# User_Interface.net
KiCad netlist of a schematic drawn in Altium Designer
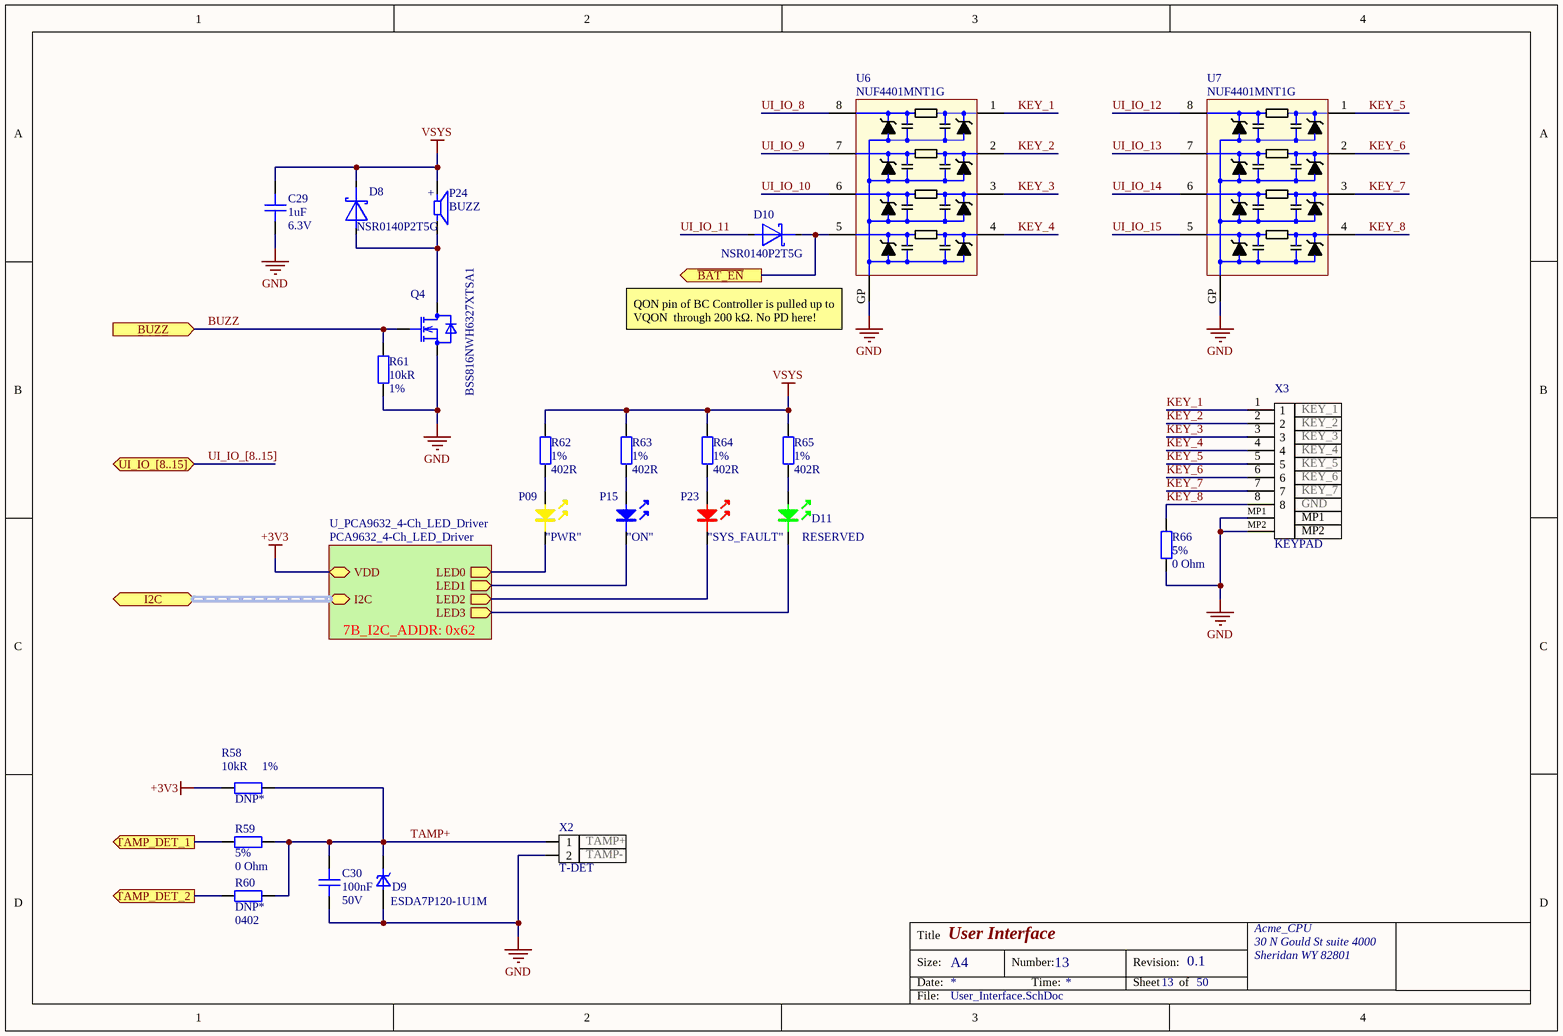
[diagram p0: User_Interface.SchDoc]

(export (version "E")
  (design (tool "Eeschema 10.0.6"))
  (components
    (comp (ref "C29")
      (value "CAP CER 1UF 6.3V X5R 0402")
      (footprint "C0402")
      (description "1µF ±10% 6.3V Ceramic Capacitor X5R 0402 (1005 Metric)")
      (fields
        (field (name "MANUFACTURER") "Yageo")
        (field (name "MANUFACTURER PART NUMBER") "CC0402KRX5R5BB105")
        (field (name "CAPACITANCE") "1uF")
        (field (name "VOLTAGE RATING") "6.3V")
      )
      (libsource (lib "capacitors_smd") (part "CAP CER 1UF 6.3V X5R 0402"))
    )
    (comp (ref "C30")
      (value "CAP CER 0.1UF 50V X7R 0402")
      (footprint "C0402")
      (description "0.1µF ±10% 50V Ceramic Capacitor X7R 0402 (1005 Metric)")
      (fields
        (field (name "MANUFACTURER") "TDK")
        (field (name "MANUFACTURER PART NUMBER") "CGA2B3X7R1H104K050BB")
        (field (name "CAPACITANCE") "100nF")
        (field (name "VOLTAGE") "50V")
      )
      (libsource (lib "capacitors_smd") (part "CAP CER 0.1UF 50V X7R 0402"))
    )
    (comp (ref "D8")
      (value "NSR0140P2T5G")
      (footprint "SODFL100X40-2N")
      (description "Diode Schottky 30V 70mA (DC) Surface Mount SOD-923")
      (fields (field (name "MANUFACTURER") "ON Semiconductor"))
      (libsource (lib "diodes_schottky") (part "DIODE SCHOTTKY 30V 70MA SOD923"))
    )
    (comp (ref "D9")
      (value "ESDA7P120-1U1M")
      (footprint "ST_QFN_1610")
      (description "11.5V Clamp 120A (8/20µs) Ipp Tvs Diode Surface Mount 1610")
      (fields (field (name "MANUFACTURER") "STMicroelectronics"))
      (libsource (lib "diodes_tvs") (part "TVS DIODE ESDA7P120-1U1M 5.5V 11.5V 1610"))
    )
    (comp (ref "D10")
      (value "NSR0140P2T5G")
      (footprint "SODFL100X40-2N")
      (description "Diode Schottky 30V 70mA (DC) Surface Mount SOD-923")
      (fields (field (name "MANUFACTURER") "ON Semiconductor"))
      (libsource (lib "diodes_schottky") (part "DIODE SCHOTTKY 30V 70MA SOD923"))
    )
    (comp (ref "D11")
      (value "RESERVED")
      (footprint "LED_0603")
      (description "Green 571nm LED Indication - Discrete 2V 0603 (1608 Metric)")
      (fields
        (field (name "MANUFACTURER") "Vishay Lite-On")
        (field (name "MANUFACTURER PART NUMBER") "LTST-C191KGKT")
      )
      (libsource (lib "diodes_led") (part "LED GREEN CLEAR 0603 SMD"))
    )
    (comp (ref "P09")
      (value "\"PWR\"")
      (footprint "LED_0603")
      (description "Yellow 591nm LED Indication - Discrete 2.1V 0603 (1608 Metric)")
      (fields
        (field (name "MANUFACTURER") "Vishay Lite-On")
        (field (name "MANUFACTURER PART NUMBER") "LTST-C191KSKT")
      )
      (libsource (lib "diodes_led") (part "LED YELLOW CLEAR 0603 SMD"))
    )
    (comp (ref "P15")
      (value "\"ON\"")
      (footprint "LED_0603")
      (description "Blue 470nm LED Indication - Discrete 3.3V 0603 (1608 Metric)")
      (fields
        (field (name "MANUFACTURER") "Vishay Lite-On")
        (field (name "MANUFACTURER PART NUMBER") "LTST-C191TBKT")
      )
      (libsource (lib "diodes_led") (part "LED BLUE CLEAR 0603 SMD"))
    )
    (comp (ref "P23")
      (value "\"SYS_FAULT\"")
      (footprint "LED_0603")
      (description "Red 631nm LED Indication - Discrete 2V 0603 (1608 Metric)")
      (fields
        (field (name "MANUFACTURER") "Vishay Lite-On")
        (field (name "MANUFACTURER PART NUMBER") "LTST-C191KRKT")
      )
      (libsource (lib "diodes_led") (part "LED RED CLEAR 0603 SMD"))
    )
    (comp (ref "P24")
      (value "BUZZ")
      (footprint "SMT-0440-S-R_PUI")
      (description "Buzzers Transducer, Externally Driven 90mA 4kHz 70dB @ 3V, 10cm Surface Mount Solder Pads")
      (fields
        (field (name "MANUFACTURER") "Projects Unlimited")
        (field (name "MANUFACTURER PART NUMBER") "SMT-0440-S-R")
      )
      (libsource (lib "BLDC_Motor_Driver") (part "AUDIO MAGNETIC XDCR 2-4V SMD"))
    )
    (comp (ref "Q4")
      (value "BSS816NWH6327XTSA1")
      (footprint "SOT-323")
      (description "N-Channel 20V 1.4A (Ta) 500mW (Ta) Surface Mount PG-SOT323-3")
      (fields (field (name "MANUFACTURER") "Infineon"))
      (libsource (lib "mosfets") (part "MOSFET BSS816NWH6327XTSA1 N-CH 20V 1.4A SOT323"))
    )
    (comp (ref "R58")
      (value "DNP*")
      (footprint "R0402")
      (description "10 kOhms ±1% 0.063W, 1/16W Chip Resistor 0402 (1005 Metric) Moisture Resistant Thick Film")
      (fields
        (field (name "MANUFACTURER") "Yageo")
        (field (name "MANUFACTURER PART NUMBER") "RC0402FR-0710KP")
        (field (name "RESISTANCE") "10kR")
        (field (name "TOLERANCE") "1%")
      )
      (libsource (lib "resistors_smd") (part "RES SMD 10K OHM 1% 1/16W 0402"))
    )
    (comp (ref "R59")
      (value "RES SMD 0 OHM JUMPER 1/16W 0402")
      (footprint "R0402")
      (description "0 Ohms Jumper 0.063W, 1/16W Chip Resistor 0402 (1005 Metric) Moisture Resistant Thick Film")
      (fields
        (field (name "MANUFACTURER") "Yageo")
        (field (name "MANUFACTURER PART NUMBER") "RC0402JR-070RL")
        (field (name "TOLERANCE") "5%")
        (field (name "RESISTANCE") "0 Ohm")
      )
      (libsource (lib "resistors_smd") (part "RES SMD 0 OHM JUMPER 1/16W 0402"))
    )
    (comp (ref "R60")
      (value "DNP*")
      (footprint "R0402")
      (description "Placeholder for a 0402 resistor")
      (fields (field (name "CASE/PACKAGE") "0402"))
      (libsource (lib "resistors_smd") (part "RES SMD NO BOM 0402"))
    )
    (comp (ref "R61")
      (value "RES SMD 10K OHM 1% 1/16W 0402")
      (footprint "R0402")
      (description "10 kOhms ±1% 0.063W, 1/16W Chip Resistor 0402 (1005 Metric) Moisture Resistant Thick Film")
      (fields
        (field (name "MANUFACTURER PART NUMBER") "RC0402FR-0710KP")
        (field (name "MANUFACTURER") "Yageo")
        (field (name "RESISTANCE") "10kR")
        (field (name "TOLERANCE") "1%")
      )
      (libsource (lib "") (part "RES SMD 10K OHM 1% 1/16W 0402_1"))
    )
    (comp (ref "R62")
      (value "RES SMD 402 OHM 1% 1/16W 0402")
      (footprint "R0402")
      (description "402 Ohms ±1% 0.063W, 1/16W Chip Resistor 0402 (1005 Metric) Moisture Resistant Thick Film")
      (fields
        (field (name "TOLERANCE") "1%")
        (field (name "MANUFACTURER") "Yageo")
        (field (name "MANUFACTURER PART NUMBER") "RC0402FR-07402RL")
        (field (name "RESISTANCE") "402R")
      )
      (libsource (lib "resistors_smd") (part "RES SMD 402 OHM 1% 1/16W 0402"))
    )
    (comp (ref "R63")
      (value "RES SMD 402 OHM 1% 1/16W 0402")
      (footprint "R0402")
      (description "402 Ohms ±1% 0.063W, 1/16W Chip Resistor 0402 (1005 Metric) Moisture Resistant Thick Film")
      (fields
        (field (name "TOLERANCE") "1%")
        (field (name "MANUFACTURER") "Yageo")
        (field (name "MANUFACTURER PART NUMBER") "RC0402FR-07402RL")
        (field (name "RESISTANCE") "402R")
      )
      (libsource (lib "resistors_smd") (part "RES SMD 402 OHM 1% 1/16W 0402"))
    )
    (comp (ref "R64")
      (value "RES SMD 402 OHM 1% 1/16W 0402")
      (footprint "R0402")
      (description "402 Ohms ±1% 0.063W, 1/16W Chip Resistor 0402 (1005 Metric) Moisture Resistant Thick Film")
      (fields
        (field (name "TOLERANCE") "1%")
        (field (name "MANUFACTURER") "Yageo")
        (field (name "MANUFACTURER PART NUMBER") "RC0402FR-07402RL")
        (field (name "RESISTANCE") "402R")
      )
      (libsource (lib "resistors_smd") (part "RES SMD 402 OHM 1% 1/16W 0402"))
    )
    (comp (ref "R65")
      (value "RES SMD 402 OHM 1% 1/16W 0402")
      (footprint "R0402")
      (description "402 Ohms ±1% 0.063W, 1/16W Chip Resistor 0402 (1005 Metric) Moisture Resistant Thick Film")
      (fields
        (field (name "TOLERANCE") "1%")
        (field (name "MANUFACTURER") "Yageo")
        (field (name "MANUFACTURER PART NUMBER") "RC0402FR-07402RL")
        (field (name "RESISTANCE") "402R")
      )
      (libsource (lib "resistors_smd") (part "RES SMD 402 OHM 1% 1/16W 0402"))
    )
    (comp (ref "R66")
      (value "RES SMD 0 OHM JUMPER 1/16W 0402")
      (footprint "R0402")
      (description "0 Ohms Jumper 0.063W, 1/16W Chip Resistor 0402 (1005 Metric) Moisture Resistant Thick Film")
      (fields
        (field (name "MANUFACTURER") "Yageo")
        (field (name "MANUFACTURER PART NUMBER") "RC0402JR-070RL")
        (field (name "TOLERANCE") "5%")
        (field (name "RESISTANCE") "0 Ohm")
      )
      (libsource (lib "") (part "RES SMD 0 OHM JUMPER 1/16W 0402_1"))
    )
    (comp (ref "U6")
      (value "NUF4401MNT1G")
      (footprint "DFN8")
      (description "EMI filter w/ ESD prot. NUF4401MN 12mm r")
      (fields (field (name "MANUFACTURER") "ON Semiconductor"))
      (libsource (lib "diodes_tvs") (part "FILTER RC(PI) 200 OHM/15PF SMD"))
    )
    (comp (ref "U7")
      (value "NUF4401MNT1G")
      (footprint "DFN8")
      (description "EMI filter w/ ESD prot. NUF4401MN 12mm r")
      (fields (field (name "MANUFACTURER") "ON Semiconductor"))
      (libsource (lib "diodes_tvs") (part "FILTER RC(PI) 200 OHM/15PF SMD"))
    )
    (comp (ref "X2")
      (value "T-DET")
      (footprint "CONN_S2B-ZR_JST")
      (description "Connector Header Through Hole, Right Angle 2 position 0.059\" (1.50mm)")
      (fields
        (field (name "MANUFACTURER") "JST")
        (field (name "MANUFACTURER PART NUMBER") "S2B-ZR(LF)(SN)")
        (field (name "PIN_1") "TAMP+")
        (field (name "PIN_2") "TAMP-")
      )
      (libsource (lib "connectors_header") (part "CONN HEADER TH R/A 2POS 1.5MM"))
    )
    (comp (ref "X3")
      (value "KEYPAD")
      (footprint "686108183522")
      (description "8 Position FFC Connector Contacts, Bottom 0.039\" (1.00mm) Surface Mount, Right Angle")
      (fields
        (field (name "PIN_7") "KEY_7")
        (field (name "PIN_1") "KEY_1")
        (field (name "PIN_2") "KEY_2")
        (field (name "PIN_3") "KEY_3")
        (field (name "PIN_4") "KEY_4")
        (field (name "PIN_5") "KEY_5")
        (field (name "PIN_6") "KEY_6")
        (field (name "PIN_8") "GND")
        (field (name "PART NUMBER") "686108183522")
        (field (name "MANUFACTURER") "Wurth Electronics")
        (field (name "PIN_MP1") "MP1")
        (field (name "PIN_MP2") "MP2")
        (field (name "PUBLISHER") "Wurth Elektronik")
      )
      (libsource (lib "connectors_ffc") (part "CONN 686108183522 FFC BTM 8POS 1MM SMD R/A"))
    )
  )
  (nets
    (net (code "2") (name "+3V3") (class "Default")
      (node (ref "R58") (pin "1") (pinfunction "1_1") (pintype "passive"))
    )
    (net (code "3") (name "/BAT_EN") (class "Default")
      (node (ref "D10") (pin "1") (pinfunction "K_1") (pintype "passive"))
      (node (ref "U6") (pin "5") (pinfunction "OUT4_5") (pintype "passive"))
    )
    (net (code "4") (name "/BUZZ") (class "Default")
      (node (ref "Q4") (pin "1") (pinfunction "G_1") (pintype "passive"))
      (node (ref "R61") (pin "1") (pinfunction "1_1") (pintype "passive"))
    )
    (net (code "6") (name "/KEY_1") (class "Default")
      (node (ref "U6") (pin "1") (pinfunction "INP1_1") (pintype "passive"))
      (node (ref "X3") (pin "1") (pinfunction "1_1") (pintype "passive"))
    )
    (net (code "7") (name "/KEY_2") (class "Default")
      (node (ref "U6") (pin "2") (pinfunction "INP2_2") (pintype "passive"))
      (node (ref "X3") (pin "2") (pinfunction "2_2") (pintype "passive"))
    )
    (net (code "8") (name "/KEY_3") (class "Default")
      (node (ref "U6") (pin "3") (pinfunction "INP3_3") (pintype "passive"))
      (node (ref "X3") (pin "3") (pinfunction "3_3") (pintype "passive"))
    )
    (net (code "9") (name "/KEY_4") (class "Default")
      (node (ref "U6") (pin "4") (pinfunction "INP4_4") (pintype "passive"))
      (node (ref "X3") (pin "4") (pinfunction "4_4") (pintype "passive"))
    )
    (net (code "10") (name "/KEY_5") (class "Default")
      (node (ref "U7") (pin "1") (pinfunction "INP1_1") (pintype "passive"))
      (node (ref "X3") (pin "5") (pinfunction "5_5") (pintype "passive"))
    )
    (net (code "11") (name "/KEY_6") (class "Default")
      (node (ref "U7") (pin "2") (pinfunction "INP2_2") (pintype "passive"))
      (node (ref "X3") (pin "6") (pinfunction "6_6") (pintype "passive"))
    )
    (net (code "12") (name "/KEY_7") (class "Default")
      (node (ref "U7") (pin "3") (pinfunction "INP3_3") (pintype "passive"))
      (node (ref "X3") (pin "7") (pinfunction "7_7") (pintype "passive"))
    )
    (net (code "13") (name "/KEY_8") (class "Default")
      (node (ref "R66") (pin "2") (pinfunction "2_2") (pintype "passive"))
      (node (ref "U7") (pin "4") (pinfunction "INP4_4") (pintype "passive"))
      (node (ref "X3") (pin "8") (pinfunction "8_8") (pintype "passive"))
    )
    (net (code "14") (name "/LED0") (class "Default")
      (node (ref "P09") (pin "1") (pinfunction "K_1") (pintype "passive"))
    )
    (net (code "15") (name "/LED1") (class "Default")
      (node (ref "P15") (pin "1") (pinfunction "K_1") (pintype "passive"))
    )
    (net (code "16") (name "/LED2") (class "Default")
      (node (ref "P23") (pin "1") (pinfunction "K_1") (pintype "passive"))
    )
    (net (code "17") (name "/LED3") (class "Default")
      (node (ref "D11") (pin "1") (pinfunction "K_1") (pintype "passive"))
    )
    (net (code "18") (name "/TAMP+") (class "Default")
      (node (ref "C30") (pin "1") (pinfunction "1_1") (pintype "passive"))
      (node (ref "D9") (pin "1") (pinfunction "K_1") (pintype "passive"))
      (node (ref "R58") (pin "2") (pinfunction "2_2") (pintype "passive"))
      (node (ref "R59") (pin "2") (pinfunction "2_2") (pintype "passive"))
      (node (ref "R60") (pin "1") (pinfunction "1_1") (pintype "passive"))
      (node (ref "X2") (pin "1") (pinfunction "1_1") (pintype "passive"))
    )
    (net (code "19") (name "/TAMP_DET_1") (class "Default")
      (node (ref "R59") (pin "1") (pinfunction "1_1") (pintype "passive"))
    )
    (net (code "20") (name "/TAMP_DET_2") (class "Default")
      (node (ref "R60") (pin "2") (pinfunction "2_2") (pintype "passive"))
    )
    (net (code "21") (name "/UI_IO_8") (class "Default")
      (node (ref "U6") (pin "8") (pinfunction "OUT1_8") (pintype "passive"))
    )
    (net (code "22") (name "/UI_IO_9") (class "Default")
      (node (ref "U6") (pin "7") (pinfunction "OUT2_7") (pintype "passive"))
    )
    (net (code "23") (name "/UI_IO_10") (class "Default")
      (node (ref "U6") (pin "6") (pinfunction "OUT3_6") (pintype "passive"))
    )
    (net (code "24") (name "/UI_IO_11") (class "Default")
      (node (ref "D10") (pin "2") (pinfunction "A_2") (pintype "passive"))
    )
    (net (code "25") (name "/UI_IO_12") (class "Default")
      (node (ref "U7") (pin "8") (pinfunction "OUT1_8") (pintype "passive"))
    )
    (net (code "26") (name "/UI_IO_13") (class "Default")
      (node (ref "U7") (pin "7") (pinfunction "OUT2_7") (pintype "passive"))
    )
    (net (code "27") (name "/UI_IO_14") (class "Default")
      (node (ref "U7") (pin "6") (pinfunction "OUT3_6") (pintype "passive"))
    )
    (net (code "28") (name "/UI_IO_15") (class "Default")
      (node (ref "U7") (pin "5") (pinfunction "OUT4_5") (pintype "passive"))
    )
    (net (code "30") (name "GND") (class "Default")
      (node (ref "C29") (pin "2") (pinfunction "2_2") (pintype "passive"))
      (node (ref "C30") (pin "2") (pinfunction "2_2") (pintype "passive"))
      (node (ref "D9") (pin "2") (pinfunction "A_2") (pintype "passive"))
      (node (ref "Q4") (pin "2") (pinfunction "S_2") (pintype "passive"))
      (node (ref "R61") (pin "2") (pinfunction "2_2") (pintype "passive"))
      (node (ref "R66") (pin "1") (pinfunction "1_1") (pintype "passive"))
      (node (ref "U6") (pin "GP") (pinfunction "GND_GP") (pintype "passive"))
      (node (ref "U7") (pin "GP") (pinfunction "GND_GP") (pintype "passive"))
      (node (ref "X2") (pin "2") (pinfunction "2_2") (pintype "passive"))
      (node (ref "X3") (pin "MP1") (pinfunction "MP1_MP1") (pintype "passive"))
      (node (ref "X3") (pin "MP2") (pinfunction "MP2_MP2") (pintype "passive"))
    )
    (net (code "31") (name "Net-(D8-A)") (class "Default")
      (node (ref "D8") (pin "2") (pinfunction "A_2") (pintype "passive"))
      (node (ref "P24") (pin "2") (pinfunction "2_2") (pintype "passive"))
      (node (ref "Q4") (pin "3") (pinfunction "D_3") (pintype "passive"))
    )
    (net (code "32") (name "Net-(D11-A)") (class "Default")
      (node (ref "D11") (pin "2") (pinfunction "A_2") (pintype "passive"))
      (node (ref "R65") (pin "1") (pinfunction "1_1") (pintype "passive"))
    )
    (net (code "33") (name "Net-(P09-A)") (class "Default")
      (node (ref "P09") (pin "2") (pinfunction "A_2") (pintype "passive"))
      (node (ref "R62") (pin "1") (pinfunction "1_1") (pintype "passive"))
    )
    (net (code "34") (name "Net-(P15-A)") (class "Default")
      (node (ref "P15") (pin "2") (pinfunction "A_2") (pintype "passive"))
      (node (ref "R63") (pin "1") (pinfunction "1_1") (pintype "passive"))
    )
    (net (code "35") (name "Net-(P23-A)") (class "Default")
      (node (ref "P23") (pin "2") (pinfunction "A_2") (pintype "passive"))
      (node (ref "R64") (pin "1") (pinfunction "1_1") (pintype "passive"))
    )
    (net (code "36") (name "VSYS") (class "Default")
      (node (ref "C29") (pin "1") (pinfunction "1_1") (pintype "passive"))
      (node (ref "D8") (pin "1") (pinfunction "K_1") (pintype "passive"))
      (node (ref "P24") (pin "1") (pinfunction "1_1") (pintype "passive"))
      (node (ref "R62") (pin "2") (pinfunction "2_2") (pintype "passive"))
      (node (ref "R63") (pin "2") (pinfunction "2_2") (pintype "passive"))
      (node (ref "R64") (pin "2") (pinfunction "2_2") (pintype "passive"))
      (node (ref "R65") (pin "2") (pinfunction "2_2") (pintype "passive"))
    )
  )
)
